# Enclosure_100x68_BEWB.net
KiCad netlist of a schematic drawn in EAGLE
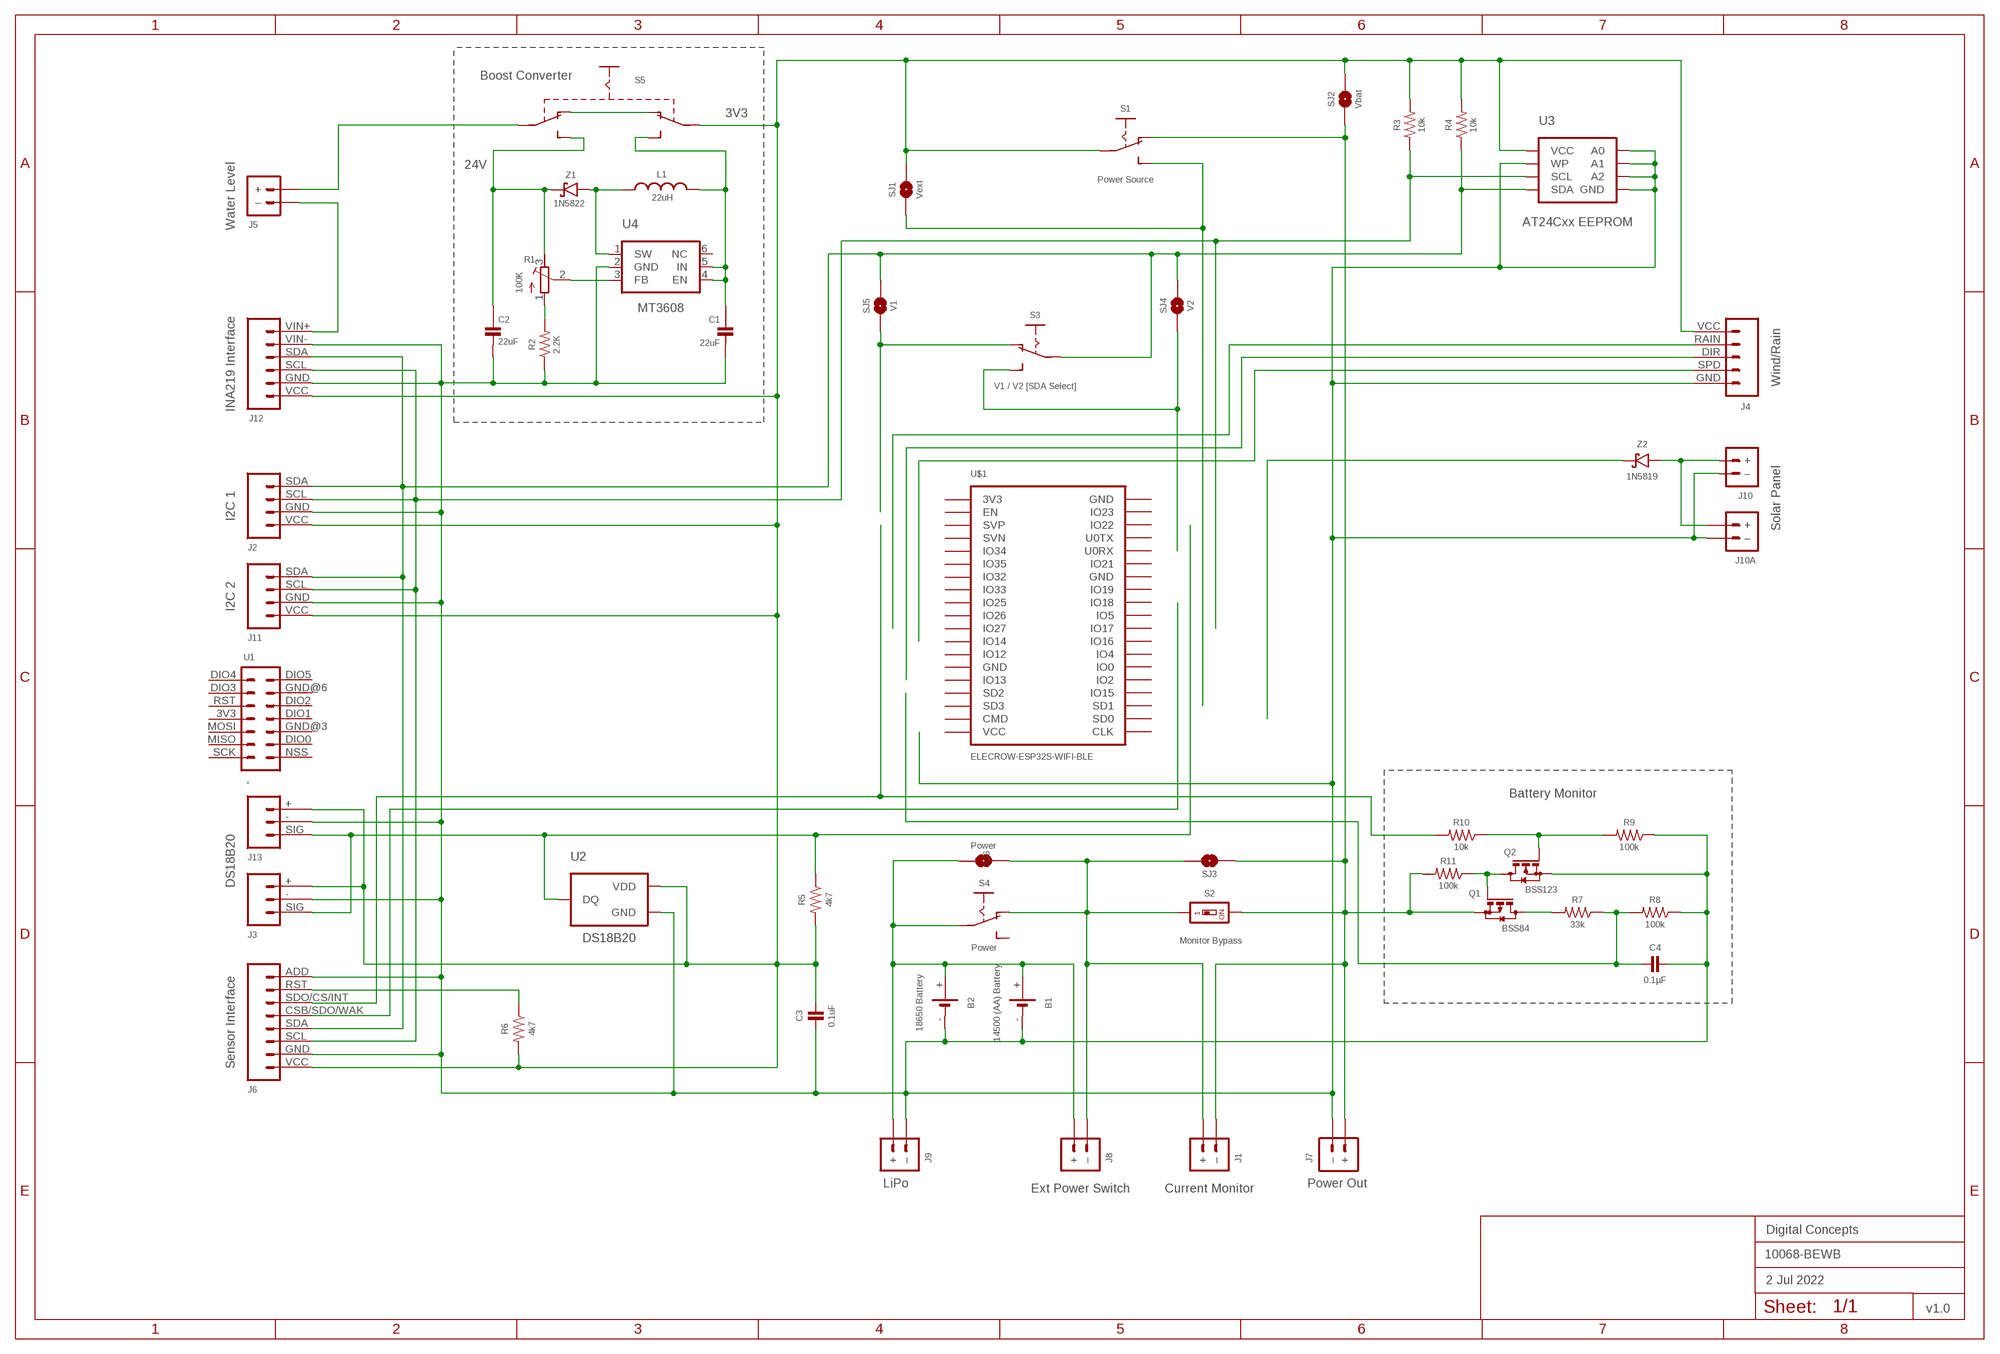
[diagram p0: schematic, sheet 1]

(export (version "E")
  (design (tool "Eeschema 10.0.6"))
  (components
    (comp (ref "B1")
      (value "14500 (AA) Battery")
      (footprint "eagle-import:BATTERY-14500")
      (libsource (lib "eagle-import") (part "BATTERY-HOLDER-14500(AA)"))
    )
    (comp (ref "B2")
      (value "18650 Battery")
      (footprint "eagle-import:BATTERY-18650")
      (libsource (lib "eagle-import") (part "BATTERY-HOLDER-18650"))
    )
    (comp (ref "C1")
      (value "22uF")
      (footprint "eagle-import:C1206")
      (libsource (lib "eagle-import") (part "CAPACITOR-1206"))
    )
    (comp (ref "C2")
      (value "22uF")
      (footprint "eagle-import:C1206")
      (libsource (lib "eagle-import") (part "CAPACITOR-1206"))
    )
    (comp (ref "C3")
      (value "0.1uF")
      (footprint "eagle-import:C0805")
      (libsource (lib "eagle-import") (part "CAPACITOR-0805"))
    )
    (comp (ref "C4")
      (value "0.1µF")
      (footprint "eagle-import:C0805")
      (libsource (lib "eagle-import") (part "CAPACITOR-0805"))
    )
    (comp (ref "J1")
      (value "Current Monitor")
      (footprint "eagle-import:JST-PH2.0-2-HORIZONTAL")
      (libsource (lib "eagle-import") (part "JST-PH2.0-2-HORIZONTALJST-PTH-2"))
    )
    (comp (ref "J2")
      (value "I2C 1")
      (footprint "eagle-import:JST-PH2.0-4-VERTICAL-I2C")
      (libsource (lib "eagle-import") (part "JST-PH2.0-4-VERTICAL-I2C"))
    )
    (comp (ref "J3")
      (value "DS18B20")
      (footprint "eagle-import:JST-PH2.0-3-VERTICAL-SIG")
      (libsource (lib "eagle-import") (part "JST-PH2.0-3-VERTICAL-DS18B20"))
    )
    (comp (ref "J4")
      (value "Wind/Rain")
      (footprint "eagle-import:JST-PH2.0-5-DUAL-WEATHER")
      (libsource (lib "eagle-import") (part "JST-PH2.0-5-DUAL-WEATHER"))
    )
    (comp (ref "J5")
      (value "Water Level")
      (footprint "eagle-import:JST-PH2.0-2-DUAL-POWER")
      (libsource (lib "eagle-import") (part "JST-PH2.0-2-DUAL-POWERJST-PTH-2"))
    )
    (comp (ref "J6")
      (value "Sensor Interface")
      (footprint "eagle-import:CONN_08-SENSOR")
      (libsource (lib "eagle-import") (part "HEADER-1X8-SENSOR"))
    )
    (comp (ref "J7")
      (value "Power Out")
      (footprint "eagle-import:JST-GH1.25-2-HORIZONTAL")
      (libsource (lib "eagle-import") (part "JST-GH1.25-2-HORIZONTAL-POWER"))
    )
    (comp (ref "J8")
      (value "Ext Power Switch")
      (footprint "eagle-import:JST-PH2.0-2-DUAL-POWER")
      (libsource (lib "eagle-import") (part "JST-PH2.0-2-DUAL-POWERJST-PTH-2"))
    )
    (comp (ref "J9")
      (value "LiPo")
      (footprint "eagle-import:JST-PH2.0-2-HORIZONTAL-POWER")
      (libsource (lib "eagle-import") (part "JST-PH2.0-2-HORIZONTAL-POWERJST-PTH-2"))
    )
    (comp (ref "J10")
      (value "Solar Panel")
      (footprint "eagle-import:JST-PH2.0-2-VERTICAL=POWER")
      (libsource (lib "eagle-import") (part "JST-PH2.0-2-VERTICAL"))
    )
    (comp (ref "J10A")
      (value "JST-PH2.0-2-HORIZONTAL-POWERJST-PTH-2")
      (footprint "eagle-import:JST-PH2.0-2-HORIZONTAL-POWER")
      (libsource (lib "eagle-import") (part "JST-PH2.0-2-HORIZONTAL-POWERJST-PTH-2"))
    )
    (comp (ref "J11")
      (value "I2C 2")
      (footprint "eagle-import:JST-PH2.0-4-HORIZONTAL")
      (libsource (lib "eagle-import") (part "JST-PH2.0-I2C-MALE-HORIZONTAL"))
    )
    (comp (ref "J12")
      (value "INA219 Interface")
      (footprint "eagle-import:CONN_06-INA219")
      (libsource (lib "eagle-import") (part "INA219-I2C-MODULE"))
    )
    (comp (ref "J13")
      (value "JST-PH2.0-3-HORIZONTAL-DS18B20")
      (footprint "eagle-import:JST-PH2.0-DS18B20-HORIZONTAL")
      (libsource (lib "eagle-import") (part "JST-PH2.0-3-HORIZONTAL-DS18B20"))
    )
    (comp (ref "L1")
      (value "22uH")
      (footprint "eagle-import:CDRH104R+")
      (libsource (lib "eagle-import") (part "INDUCTOR-CDRH104R+L5038P"))
    )
    (comp (ref "Q1")
      (value "BSS84")
      (footprint "eagle-import:SOT23-3")
      (libsource (lib "eagle-import") (part "BSS84"))
    )
    (comp (ref "Q2")
      (value "BSS123")
      (footprint "eagle-import:SOT23-3")
      (libsource (lib "eagle-import") (part "MOSFET-BSS123"))
    )
    (comp (ref "R1")
      (value "100K")
      (footprint "eagle-import:RTRIM64P")
      (libsource (lib "eagle-import") (part "RESISTOR-TRIMM-BAOTER-HORIZONTAL"))
    )
    (comp (ref "R2")
      (value "2.2K")
      (footprint "eagle-import:R0805")
      (libsource (lib "eagle-import") (part "RESISTORR0805"))
    )
    (comp (ref "R3")
      (value "10k")
      (footprint "eagle-import:R0805")
      (libsource (lib "eagle-import") (part "RESISTORR0805"))
    )
    (comp (ref "R4")
      (value "10k")
      (footprint "eagle-import:R0805")
      (libsource (lib "eagle-import") (part "RESISTORR0805"))
    )
    (comp (ref "R5")
      (value "4k7")
      (footprint "eagle-import:R0805")
      (libsource (lib "eagle-import") (part "RESISTORR0805"))
    )
    (comp (ref "R6")
      (value "4k7")
      (footprint "eagle-import:R0805")
      (libsource (lib "eagle-import") (part "RESISTORR0805"))
    )
    (comp (ref "R7")
      (value "33k")
      (footprint "eagle-import:R0805")
      (libsource (lib "eagle-import") (part "RESISTORR0805"))
    )
    (comp (ref "R8")
      (value "100k")
      (footprint "eagle-import:R0805")
      (libsource (lib "eagle-import") (part "RESISTORR0805"))
    )
    (comp (ref "R9")
      (value "100k")
      (footprint "eagle-import:R0805")
      (libsource (lib "eagle-import") (part "RESISTORR0805"))
    )
    (comp (ref "R10")
      (value "10k")
      (footprint "eagle-import:R0805")
      (libsource (lib "eagle-import") (part "RESISTORR0805"))
    )
    (comp (ref "R11")
      (value "100k")
      (footprint "eagle-import:R0805")
      (libsource (lib "eagle-import") (part "RESISTORR0805"))
    )
    (comp (ref "S1")
      (value "Power Source")
      (footprint "eagle-import:SWITCH-SPDT-SMT")
      (libsource (lib "eagle-import") (part "SWITCH-SLIDE-SPDT-SMT"))
    )
    (comp (ref "S2")
      (value "Monitor Bypass")
      (footprint "eagle-import:SMD-001")
      (libsource (lib "eagle-import") (part "SWITCH-DIP-SWS001"))
    )
    (comp (ref "S3")
      (value "V1 / V2 [SDA Select]")
      (footprint "eagle-import:SWITCH-SPDT-SMT")
      (libsource (lib "eagle-import") (part "SWITCH-SLIDE-SPDT-SMT"))
    )
    (comp (ref "S4")
      (value "Power")
      (footprint "eagle-import:SWITCH-SPDT-PTH")
      (libsource (lib "eagle-import") (part "SWITCH-SLIDE-SPDT-PTH"))
    )
    (comp (ref "S5")
      (value "SWITCH-SLIDE-DPDT-PTH-S")
      (footprint "eagle-import:SWITCH-DPDT-PTH")
      (libsource (lib "eagle-import") (part "SWITCH-SLIDE-DPDT-PTH-S"))
    )
    (comp (ref "SJ1")
      (value "Vext")
      (footprint "eagle-import:SJ")
      (libsource (lib "eagle-import") (part "SJ"))
    )
    (comp (ref "SJ2")
      (value "Vbat")
      (footprint "eagle-import:SJ-VIA-2")
      (libsource (lib "eagle-import") (part "SJ-V-2"))
    )
    (comp (ref "SJ3")
      (value "Monitor")
      (footprint "eagle-import:SJ")
      (libsource (lib "eagle-import") (part "SJ"))
    )
    (comp (ref "SJ4") (value "V2") (footprint "eagle-import:SJ") (libsource (lib "eagle-import") (part "SJ")))
    (comp (ref "SJ5") (value "V1") (footprint "eagle-import:SJ") (libsource (lib "eagle-import") (part "SJ")))
    (comp (ref "SJ6")
      (value "Power")
      (footprint "eagle-import:SJ")
      (libsource (lib "eagle-import") (part "SJ"))
    )
    (comp (ref "U$1")
      (value "ELECROW-ESP32S-WIFI-BLE")
      (footprint "eagle-import:ELECROW-ESP32S-WIFI-BLE")
      (libsource (lib "eagle-import") (part "ELECROW-ESP32S-WIFI-BLE"))
    )
    (comp (ref "U1")
      (value "RFM95W-PI-HEADER")
      (footprint "eagle-import:RFM95W-PI")
      (libsource (lib "eagle-import") (part "RFM95W-PI-HEADER"))
    )
    (comp (ref "U2")
      (value "DS18B20")
      (footprint "eagle-import:TO-92")
      (fields (field (name "MF") "Maxim Integrated"))
      (libsource (lib "eagle-import") (part "THERMOMETER-DS18B20"))
    )
    (comp (ref "U3")
      (value "AT24Cxx EEPROM")
      (footprint "eagle-import:SOP-8")
      (libsource (lib "eagle-import") (part "AT24CXX-EEPROM"))
    )
    (comp (ref "U4")
      (value "MT3608")
      (footprint "eagle-import:SOT-23-6")
      (libsource (lib "eagle-import") (part "MT3608"))
    )
    (comp (ref "Z1")
      (value "1N5822")
      (footprint "eagle-import:DIODE_SMB")
      (libsource (lib "eagle-import") (part "DIODE-SCHOTTKY-1N5822"))
    )
    (comp (ref "Z2")
      (value "1N5819")
      (footprint "eagle-import:SOD-123")
      (libsource (lib "eagle-import") (part "1N5819-SOD-123"))
    )
  )
  (nets
    (net (code "1") (name "Net-(C4-Pad1)") (class "Default")
      (node (ref "C4") (pin "1") (pinfunction "1_1") (pintype "passive"))
      (node (ref "R7") (pin "1") (pinfunction "1_1") (pintype "passive"))
      (node (ref "R8") (pin "2") (pinfunction "2_2") (pintype "passive"))
    )
    (net (code "2") (name "Net-(J1-+)") (class "Default")
      (node (ref "J1") (pin "1") (pinfunction "+_1") (pintype "power_in"))
      (node (ref "J8") (pin "-") (pinfunction "–_-") (pintype "power_in"))
      (node (ref "S2") (pin "1") (pinfunction "1_1") (pintype "passive"))
      (node (ref "S4") (pin "1") (pinfunction "O_1") (pintype "passive"))
      (node (ref "SJ3") (pin "2") (pinfunction "2_2") (pintype "passive"))
      (node (ref "SJ6") (pin "1") (pinfunction "1_1") (pintype "passive"))
    )
    (net (code "3") (name "Net-(J1-–)") (class "Default")
      (node (ref "J1") (pin "2") (pinfunction "–_2") (pintype "power_in"))
      (node (ref "J7") (pin "+") (pinfunction "+_+") (pintype "power_in"))
      (node (ref "Q1") (pin "2") (pinfunction "S_2") (pintype "passive"))
      (node (ref "R11") (pin "2") (pinfunction "2_2") (pintype "passive"))
      (node (ref "S1") (pin "1") (pinfunction "O_1") (pintype "passive"))
      (node (ref "S2") (pin "2") (pinfunction "2_2") (pintype "passive"))
      (node (ref "SJ2") (pin "1") (pinfunction "1_1") (pintype "passive"))
      (node (ref "SJ3") (pin "1") (pinfunction "1_1") (pintype "passive"))
    )
    (net (code "4") (name "Net-(J6-6)") (class "Default")
      (node (ref "J6") (pin "SDO/CS/INT") (pinfunction "6_SDO/CS/INT") (pintype "passive"))
      (node (ref "R10") (pin "2") (pinfunction "2_2") (pintype "passive"))
    )
    (net (code "5") (name "Net-(J6-7)") (class "Default")
      (node (ref "J6") (pin "RST") (pinfunction "7_RST") (pintype "passive"))
      (node (ref "R6") (pin "1") (pinfunction "1_1") (pintype "passive"))
    )
    (net (code "6") (name "Net-(J10-Pad+)") (class "Default")
      (node (ref "J10") (pin "+") (pinfunction "+_+") (pintype "power_in"))
      (node (ref "J10A") (pin "+") (pinfunction "+_+") (pintype "power_in"))
      (node (ref "Z2") (pin "A") (pinfunction "A_A") (pintype "passive"))
    )
    (net (code "7") (name "Net-(J10-–)") (class "Default")
      (node (ref "B1") (pin "-") (pinfunction "-_-") (pintype "power_in"))
      (node (ref "B2") (pin "-") (pinfunction "-_-") (pintype "power_in"))
      (node (ref "C1") (pin "2") (pinfunction "2_2") (pintype "passive"))
      (node (ref "C2") (pin "2") (pinfunction "2_2") (pintype "passive"))
      (node (ref "C3") (pin "2") (pinfunction "2_2") (pintype "passive"))
      (node (ref "C4") (pin "2") (pinfunction "2_2") (pintype "passive"))
      (node (ref "J10") (pin "-") (pinfunction "–_-") (pintype "power_in"))
      (node (ref "J10A") (pin "-") (pinfunction "–_-") (pintype "power_in"))
      (node (ref "J11") (pin "GND") (pinfunction "2_GND") (pintype "passive"))
      (node (ref "J12") (pin "GND") (pinfunction "2_GND") (pintype "passive"))
      (node (ref "J12") (pin "VIN-") (pinfunction "5_VIN-") (pintype "passive"))
      (node (ref "J13") (pin "-") (pinfunction "2_-") (pintype "passive"))
      (node (ref "J2") (pin "GND") (pinfunction "3_GND") (pintype "passive"))
      (node (ref "J3") (pin "-") (pinfunction "2_-") (pintype "passive"))
      (node (ref "J4") (pin "GND") (pinfunction "5_GND") (pintype "passive"))
      (node (ref "J6") (pin "ADD") (pinfunction "8_ADD") (pintype "passive"))
      (node (ref "J6") (pin "GND") (pinfunction "2_GND") (pintype "passive"))
      (node (ref "J7") (pin "-") (pinfunction "–_-") (pintype "power_in"))
      (node (ref "J9") (pin "-") (pinfunction "–_-") (pintype "power_in"))
      (node (ref "Q2") (pin "2") (pinfunction "S_2") (pintype "passive"))
      (node (ref "R2") (pin "1") (pinfunction "1_1") (pintype "passive"))
      (node (ref "R8") (pin "1") (pinfunction "1_1") (pintype "passive"))
      (node (ref "R9") (pin "1") (pinfunction "1_1") (pintype "passive"))
      (node (ref "U2") (pin "1") (pinfunction "GND_1") (pintype "power_in"))
      (node (ref "U3") (pin "P$1") (pinfunction "A0_P$1") (pintype "bidirectional"))
      (node (ref "U3") (pin "P$2") (pinfunction "A1_P$2") (pintype "bidirectional"))
      (node (ref "U3") (pin "P$3") (pinfunction "A2_P$3") (pintype "bidirectional"))
      (node (ref "U3") (pin "P$4") (pinfunction "GND_P$4") (pintype "bidirectional"))
      (node (ref "U3") (pin "P$7") (pinfunction "WP_P$7") (pintype "bidirectional"))
      (node (ref "U4") (pin "2") (pinfunction "GND_2") (pintype "power_in"))
    )
    (net (code "8") (name "Net-(J11-1)") (class "Default")
      (node (ref "C3") (pin "1") (pinfunction "1_1") (pintype "passive"))
      (node (ref "J11") (pin "VCC") (pinfunction "1_VCC") (pintype "passive"))
      (node (ref "J12") (pin "VCC") (pinfunction "1_VCC") (pintype "passive"))
      (node (ref "J13") (pin "+") (pinfunction "3_+") (pintype "passive"))
      (node (ref "J2") (pin "VCC") (pinfunction "4_VCC") (pintype "passive"))
      (node (ref "J3") (pin "+") (pinfunction "3_+") (pintype "passive"))
      (node (ref "J4") (pin "VCC") (pinfunction "1_VCC") (pintype "passive"))
      (node (ref "J6") (pin "VCC") (pinfunction "1_VCC") (pintype "passive"))
      (node (ref "R3") (pin "2") (pinfunction "2_2") (pintype "passive"))
      (node (ref "R4") (pin "2") (pinfunction "2_2") (pintype "passive"))
      (node (ref "R5") (pin "2") (pinfunction "2_2") (pintype "passive"))
      (node (ref "R6") (pin "2") (pinfunction "2_2") (pintype "passive"))
      (node (ref "S1") (pin "2") (pinfunction "P_2") (pintype "passive"))
      (node (ref "S5") (pin "P$5") (pinfunction "P2_P$5") (pintype "passive"))
      (node (ref "SJ1") (pin "2") (pinfunction "2_2") (pintype "passive"))
      (node (ref "SJ2") (pin "2") (pinfunction "2_2") (pintype "passive"))
      (node (ref "SJ2") (pin "2@V") (pinfunction "2_2@V") (pintype "passive"))
      (node (ref "U2") (pin "3") (pinfunction "VDD_3") (pintype "power_in"))
      (node (ref "U3") (pin "P$8") (pinfunction "VCC_P$8") (pintype "bidirectional"))
    )
    (net (code "9") (name "Net-(J11-3)") (class "Default")
      (node (ref "J11") (pin "SCL") (pinfunction "3_SCL") (pintype "passive"))
      (node (ref "J12") (pin "SCL") (pinfunction "3_SCL") (pintype "passive"))
      (node (ref "J2") (pin "SCL") (pinfunction "2_SCL") (pintype "passive"))
      (node (ref "J6") (pin "SCL") (pinfunction "3_SCL") (pintype "passive"))
      (node (ref "R3") (pin "1") (pinfunction "1_1") (pintype "passive"))
      (node (ref "U3") (pin "P$6") (pinfunction "SCL_P$6") (pintype "bidirectional"))
    )
    (net (code "10") (name "Net-(J11-4)") (class "Default")
      (node (ref "J11") (pin "SDA") (pinfunction "4_SDA") (pintype "passive"))
      (node (ref "J12") (pin "SDA") (pinfunction "4_SDA") (pintype "passive"))
      (node (ref "J2") (pin "SDA") (pinfunction "1_SDA") (pintype "passive"))
      (node (ref "J6") (pin "SDA") (pinfunction "4_SDA") (pintype "passive"))
      (node (ref "R4") (pin "1") (pinfunction "1_1") (pintype "passive"))
      (node (ref "S3") (pin "2") (pinfunction "P_2") (pintype "passive"))
      (node (ref "SJ4") (pin "2") (pinfunction "2_2") (pintype "passive"))
      (node (ref "SJ5") (pin "2") (pinfunction "2_2") (pintype "passive"))
      (node (ref "U3") (pin "P$5") (pinfunction "SDA_P$5") (pintype "bidirectional"))
    )
    (net (code "11") (name "Net-(J12-6)") (class "Default")
      (node (ref "J12") (pin "VIN+") (pinfunction "6_VIN+") (pintype "passive"))
      (node (ref "J5") (pin "-") (pinfunction "–_-") (pintype "power_in"))
    )
    (net (code "12") (name "Net-(J13-1)") (class "Default")
      (node (ref "J13") (pin "SIG") (pinfunction "1_SIG") (pintype "passive"))
      (node (ref "J3") (pin "SIG") (pinfunction "1_SIG") (pintype "passive"))
      (node (ref "R5") (pin "1") (pinfunction "1_1") (pintype "passive"))
      (node (ref "U2") (pin "2") (pinfunction "DQ_2") (pintype "bidirectional"))
    )
    (net (code "13") (name "Net-(Q1-D)") (class "Default")
      (node (ref "Q1") (pin "3") (pinfunction "D_3") (pintype "passive"))
      (node (ref "R7") (pin "2") (pinfunction "2_2") (pintype "passive"))
    )
    (net (code "14") (name "Net-(Q1-G)") (class "Default")
      (node (ref "Q1") (pin "1") (pinfunction "G_1") (pintype "passive"))
      (node (ref "Q2") (pin "3") (pinfunction "D_3") (pintype "passive"))
      (node (ref "R11") (pin "1") (pinfunction "1_1") (pintype "passive"))
    )
    (net (code "15") (name "Net-(Q2-G)") (class "Default")
      (node (ref "Q2") (pin "1") (pinfunction "G_1") (pintype "passive"))
      (node (ref "R10") (pin "1") (pinfunction "1_1") (pintype "passive"))
      (node (ref "R9") (pin "2") (pinfunction "2_2") (pintype "passive"))
    )
    (net (code "16") (name "Net-(R1-A)") (class "Default")
      (node (ref "R1") (pin "1") (pinfunction "A_1") (pintype "passive"))
      (node (ref "R2") (pin "2") (pinfunction "2_2") (pintype "passive"))
    )
    (net (code "17") (name "Net-(R1-E)") (class "Default")
      (node (ref "C2") (pin "1") (pinfunction "1_1") (pintype "passive"))
      (node (ref "R1") (pin "3") (pinfunction "E_3") (pintype "passive"))
      (node (ref "S5") (pin "P$3") (pinfunction "S1_P$3") (pintype "passive"))
      (node (ref "Z1") (pin "C") (pinfunction "C_C") (pintype "passive"))
    )
    (net (code "18") (name "Net-(R1-S)") (class "Default")
      (node (ref "R1") (pin "2") (pinfunction "S_2") (pintype "passive"))
      (node (ref "U4") (pin "3") (pinfunction "FB_3") (pintype "input"))
    )
    (net (code "19") (name "Net-(S1-S)") (class "Default")
      (node (ref "S1") (pin "3") (pinfunction "S_3") (pintype "passive"))
      (node (ref "SJ1") (pin "1") (pinfunction "1_1") (pintype "passive"))
    )
    (net (code "20") (name "Net-(S3-O)") (class "Default")
      (node (ref "S3") (pin "1") (pinfunction "O_1") (pintype "passive"))
      (node (ref "SJ5") (pin "1") (pinfunction "1_1") (pintype "passive"))
    )
    (net (code "21") (name "Net-(S3-S)") (class "Default")
      (node (ref "S3") (pin "3") (pinfunction "S_3") (pintype "passive"))
      (node (ref "SJ4") (pin "1") (pinfunction "1_1") (pintype "passive"))
    )
    (net (code "22") (name "Net-(S4-P)") (class "Default")
      (node (ref "B1") (pin "+") (pinfunction "+_+") (pintype "power_in"))
      (node (ref "B2") (pin "+") (pinfunction "+_+") (pintype "power_in"))
      (node (ref "J8") (pin "+") (pinfunction "+_+") (pintype "power_in"))
      (node (ref "J9") (pin "+") (pinfunction "+_+") (pintype "power_in"))
      (node (ref "S4") (pin "2") (pinfunction "P_2") (pintype "passive"))
      (node (ref "SJ6") (pin "2") (pinfunction "2_2") (pintype "passive"))
    )
    (net (code "23") (name "Net-(S5-O1)") (class "Default")
      (node (ref "S5") (pin "P$1") (pinfunction "O1_P$1") (pintype "passive"))
      (node (ref "S5") (pin "P$4") (pinfunction "O2_P$4") (pintype "passive"))
    )
    (net (code "24") (name "Net-(S5-P1)") (class "Default")
      (node (ref "J5") (pin "+") (pinfunction "+_+") (pintype "power_in"))
      (node (ref "S5") (pin "P$2") (pinfunction "P1_P$2") (pintype "passive"))
    )
    (net (code "25") (name "Net-(S5-S2)") (class "Default")
      (node (ref "C1") (pin "1") (pinfunction "1_1") (pintype "passive"))
      (node (ref "L1") (pin "2") (pinfunction "2_2") (pintype "passive"))
      (node (ref "S5") (pin "P$6") (pinfunction "S2_P$6") (pintype "passive"))
      (node (ref "U4") (pin "4") (pinfunction "EN_4") (pintype "input"))
      (node (ref "U4") (pin "5") (pinfunction "IN_5") (pintype "power_in"))
    )
    (net (code "26") (name "Net-(U4-SW)") (class "Default")
      (node (ref "L1") (pin "1") (pinfunction "1_1") (pintype "passive"))
      (node (ref "U4") (pin "1") (pinfunction "SW_1") (pintype "power_in"))
      (node (ref "Z1") (pin "A") (pinfunction "A_A") (pintype "passive"))
    )
    (net (code "27") (name "unconnected-(J4-2-PadRAIN)") (class "Default")
      (node (ref "J4") (pin "RAIN") (pinfunction "2_RAIN") (pintype "passive"))
    )
    (net (code "28") (name "unconnected-(J4-3-PadDIR)") (class "Default")
      (node (ref "J4") (pin "DIR") (pinfunction "3_DIR") (pintype "passive"))
    )
    (net (code "29") (name "unconnected-(J4-4-PadSPD)") (class "Default")
      (node (ref "J4") (pin "SPD") (pinfunction "4_SPD") (pintype "passive"))
    )
    (net (code "30") (name "unconnected-(J6-5-PadCSB{slash}SDO{slash}WAK)") (class "Default")
      (node (ref "J6") (pin "CSB/SDO/WAK") (pinfunction "5_CSB/SDO/WAK") (pintype "passive"))
    )
    (net (code "31") (name "unconnected-(S4-S-Pad3)") (class "Default")
      (node (ref "S4") (pin "3") (pinfunction "S_3") (pintype "passive"))
    )
    (net (code "32") (name "unconnected-(U$1-GND-PadGND@13)") (class "Default")
      (node (ref "U$1") (pin "GND@13") (pinfunction "GND_GND@13") (pintype "bidirectional"))
    )
    (net (code "33") (name "unconnected-(U$1-GND-PadGND@19)") (class "Default")
      (node (ref "U$1") (pin "GND@19") (pinfunction "GND_GND@19") (pintype "bidirectional"))
    )
    (net (code "34") (name "unconnected-(U$1-GND-PadGND@33)") (class "Default")
      (node (ref "U$1") (pin "GND@33") (pinfunction "GND_GND@33") (pintype "bidirectional"))
    )
    (net (code "35") (name "unconnected-(U$1-Pad3V3)") (class "Default")
      (node (ref "U$1") (pin "3V3") (pinfunction "3V3_3V3") (pintype "bidirectional"))
    )
    (net (code "36") (name "unconnected-(U$1-PadCLK)") (class "Default")
      (node (ref "U$1") (pin "CLK") (pinfunction "CLK_CLK") (pintype "bidirectional"))
    )
    (net (code "37") (name "unconnected-(U$1-PadCMD)") (class "Default")
      (node (ref "U$1") (pin "CMD") (pinfunction "CMD_CMD") (pintype "bidirectional"))
    )
    (net (code "38") (name "unconnected-(U$1-PadEN)") (class "Default")
      (node (ref "U$1") (pin "EN") (pinfunction "EN_EN") (pintype "bidirectional"))
    )
    (net (code "39") (name "unconnected-(U$1-PadIO0)") (class "Default")
      (node (ref "U$1") (pin "IO0") (pinfunction "IO0_IO0") (pintype "bidirectional"))
    )
    (net (code "40") (name "unconnected-(U$1-PadIO2)") (class "Default")
      (node (ref "U$1") (pin "IO2") (pinfunction "IO2_IO2") (pintype "bidirectional"))
    )
    (net (code "41") (name "unconnected-(U$1-PadIO4)") (class "Default")
      (node (ref "U$1") (pin "IO4") (pinfunction "IO4_IO4") (pintype "bidirectional"))
    )
    (net (code "42") (name "unconnected-(U$1-PadIO5)") (class "Default")
      (node (ref "U$1") (pin "IO5") (pinfunction "IO5_IO5") (pintype "bidirectional"))
    )
    (net (code "43") (name "unconnected-(U$1-PadIO12)") (class "Default")
      (node (ref "U$1") (pin "IO12") (pinfunction "IO12_IO12") (pintype "bidirectional"))
    )
    (net (code "44") (name "unconnected-(U$1-PadIO13)") (class "Default")
      (node (ref "U$1") (pin "IO13") (pinfunction "IO13_IO13") (pintype "bidirectional"))
    )
    (net (code "45") (name "unconnected-(U$1-PadIO14)") (class "Default")
      (node (ref "U$1") (pin "IO14") (pinfunction "IO14_IO14") (pintype "bidirectional"))
    )
    (net (code "46") (name "unconnected-(U$1-PadIO15)") (class "Default")
      (node (ref "U$1") (pin "IO15") (pinfunction "IO15_IO15") (pintype "bidirectional"))
    )
    (net (code "47") (name "unconnected-(U$1-PadIO16)") (class "Default")
      (node (ref "U$1") (pin "IO16") (pinfunction "IO16_IO16") (pintype "bidirectional"))
    )
    (net (code "48") (name "unconnected-(U$1-PadIO17)") (class "Default")
      (node (ref "U$1") (pin "IO17") (pinfunction "IO17_IO17") (pintype "bidirectional"))
    )
    (net (code "49") (name "unconnected-(U$1-PadIO18)") (class "Default")
      (node (ref "U$1") (pin "IO18") (pinfunction "IO18_IO18") (pintype "bidirectional"))
    )
    (net (code "50") (name "unconnected-(U$1-PadIO19)") (class "Default")
      (node (ref "U$1") (pin "IO19") (pinfunction "IO19_IO19") (pintype "bidirectional"))
    )
    (net (code "51") (name "unconnected-(U$1-PadIO21)") (class "Default")
      (node (ref "U$1") (pin "IO21") (pinfunction "IO21_IO21") (pintype "bidirectional"))
    )
    (net (code "52") (name "unconnected-(U$1-PadIO22)") (class "Default")
      (node (ref "U$1") (pin "IO22") (pinfunction "IO22_IO22") (pintype "bidirectional"))
    )
    (net (code "53") (name "unconnected-(U$1-PadIO23)") (class "Default")
      (node (ref "U$1") (pin "IO23") (pinfunction "IO23_IO23") (pintype "bidirectional"))
    )
    (net (code "54") (name "unconnected-(U$1-PadIO25)") (class "Default")
      (node (ref "U$1") (pin "IO25") (pinfunction "IO25_IO25") (pintype "bidirectional"))
    )
    (net (code "55") (name "unconnected-(U$1-PadIO26)") (class "Default")
      (node (ref "U$1") (pin "IO26") (pinfunction "IO26_IO26") (pintype "bidirectional"))
    )
    (net (code "56") (name "unconnected-(U$1-PadIO27)") (class "Default")
      (node (ref "U$1") (pin "IO27") (pinfunction "IO27_IO27") (pintype "bidirectional"))
    )
    (net (code "57") (name "unconnected-(U$1-PadIO32)") (class "Default")
      (node (ref "U$1") (pin "IO32") (pinfunction "IO32_IO32") (pintype "bidirectional"))
    )
    (net (code "58") (name "unconnected-(U$1-PadIO33)") (class "Default")
      (node (ref "U$1") (pin "IO33") (pinfunction "IO33_IO33") (pintype "bidirectional"))
    )
    (net (code "59") (name "unconnected-(U$1-PadIO34)") (class "Default")
      (node (ref "U$1") (pin "IO34") (pinfunction "IO34_IO34") (pintype "bidirectional"))
    )
    (net (code "60") (name "unconnected-(U$1-PadIO35)") (class "Default")
      (node (ref "U$1") (pin "IO35") (pinfunction "IO35_IO35") (pintype "bidirectional"))
    )
    (net (code "61") (name "unconnected-(U$1-PadSD0)") (class "Default")
      (node (ref "U$1") (pin "SD0") (pinfunction "SD0_SD0") (pintype "bidirectional"))
    )
    (net (code "62") (name "unconnected-(U$1-PadSD1)") (class "Default")
      (node (ref "U$1") (pin "SD1") (pinfunction "SD1_SD1") (pintype "bidirectional"))
    )
    (net (code "63") (name "unconnected-(U$1-PadSD2)") (class "Default")
      (node (ref "U$1") (pin "SD2") (pinfunction "SD2_SD2") (pintype "bidirectional"))
    )
    (net (code "64") (name "unconnected-(U$1-PadSD3)") (class "Default")
      (node (ref "U$1") (pin "SD3") (pinfunction "SD3_SD3") (pintype "bidirectional"))
    )
    (net (code "65") (name "unconnected-(U$1-PadSVN)") (class "Default")
      (node (ref "U$1") (pin "SVN") (pinfunction "SVN_SVN") (pintype "bidirectional"))
    )
    (net (code "66") (name "unconnected-(U$1-PadSVP)") (class "Default")
      (node (ref "U$1") (pin "SVP") (pinfunction "SVP_SVP") (pintype "bidirectional"))
    )
    (net (code "67") (name "unconnected-(U$1-PadU0RX)") (class "Default")
      (node (ref "U$1") (pin "U0RX") (pinfunction "U0RX_U0RX") (pintype "bidirectional"))
    )
    (net (code "68") (name "unconnected-(U$1-PadU0TX)") (class "Default")
      (node (ref "U$1") (pin "U0TX") (pinfunction "U0TX_U0TX") (pintype "bidirectional"))
    )
    (net (code "69") (name "unconnected-(U$1-PadVCC)") (class "Default")
      (node (ref "U$1") (pin "VCC") (pinfunction "VCC_VCC") (pintype "bidirectional"))
    )
    (net (code "70") (name "unconnected-(U1-1-PadNSS)") (class "Default")
      (node (ref "U1") (pin "NSS") (pinfunction "1_NSS") (pintype "passive"))
    )
    (net (code "71") (name "unconnected-(U1-2-PadDIO0)") (class "Default")
      (node (ref "U1") (pin "DIO0") (pinfunction "2_DIO0") (pintype "passive"))
    )
    (net (code "72") (name "unconnected-(U1-3-PadGND@3)") (class "Default")
      (node (ref "U1") (pin "GND@3") (pinfunction "3_GND@3") (pintype "passive"))
    )
    (net (code "73") (name "unconnected-(U1-4-PadDIO1)") (class "Default")
      (node (ref "U1") (pin "DIO1") (pinfunction "4_DIO1") (pintype "passive"))
    )
    (net (code "74") (name "unconnected-(U1-5-PadDIO2)") (class "Default")
      (node (ref "U1") (pin "DIO2") (pinfunction "5_DIO2") (pintype "passive"))
    )
    (net (code "75") (name "unconnected-(U1-6-PadGND@6)") (class "Default")
      (node (ref "U1") (pin "GND@6") (pinfunction "6_GND@6") (pintype "passive"))
    )
    (net (code "76") (name "unconnected-(U1-7-PadDIO5)") (class "Default")
      (node (ref "U1") (pin "DIO5") (pinfunction "7_DIO5") (pintype "passive"))
    )
    (net (code "77") (name "unconnected-(U1-8-PadDIO4)") (class "Default")
      (node (ref "U1") (pin "DIO4") (pinfunction "8_DIO4") (pintype "passive"))
    )
    (net (code "78") (name "unconnected-(U1-9-PadDIO3)") (class "Default")
      (node (ref "U1") (pin "DIO3") (pinfunction "9_DIO3") (pintype "passive"))
    )
    (net (code "79") (name "unconnected-(U1-10-PadRST)") (class "Default")
      (node (ref "U1") (pin "RST") (pinfunction "10_RST") (pintype "passive"))
    )
    (net (code "80") (name "unconnected-(U1-11-Pad3V3)") (class "Default")
      (node (ref "U1") (pin "3V3") (pinfunction "11_3V3") (pintype "passive"))
    )
    (net (code "81") (name "unconnected-(U1-12-PadMOSI)") (class "Default")
      (node (ref "U1") (pin "MOSI") (pinfunction "12_MOSI") (pintype "passive"))
    )
    (net (code "82") (name "unconnected-(U1-13-PadMISO)") (class "Default")
      (node (ref "U1") (pin "MISO") (pinfunction "13_MISO") (pintype "passive"))
    )
    (net (code "83") (name "unconnected-(U1-14-PadSCK)") (class "Default")
      (node (ref "U1") (pin "SCK") (pinfunction "14_SCK") (pintype "passive"))
    )
    (net (code "84") (name "unconnected-(U4-NC-Pad6)") (class "Default")
      (node (ref "U4") (pin "6") (pinfunction "NC_6") (pintype "no_connect"))
    )
    (net (code "85") (name "unconnected-(Z2-PadC)") (class "Default")
      (node (ref "Z2") (pin "C") (pinfunction "C_C") (pintype "passive"))
    )
  )
)
